# OPENMV4_BASE.net
KiCad netlist of a schematic drawn in Altium Designer
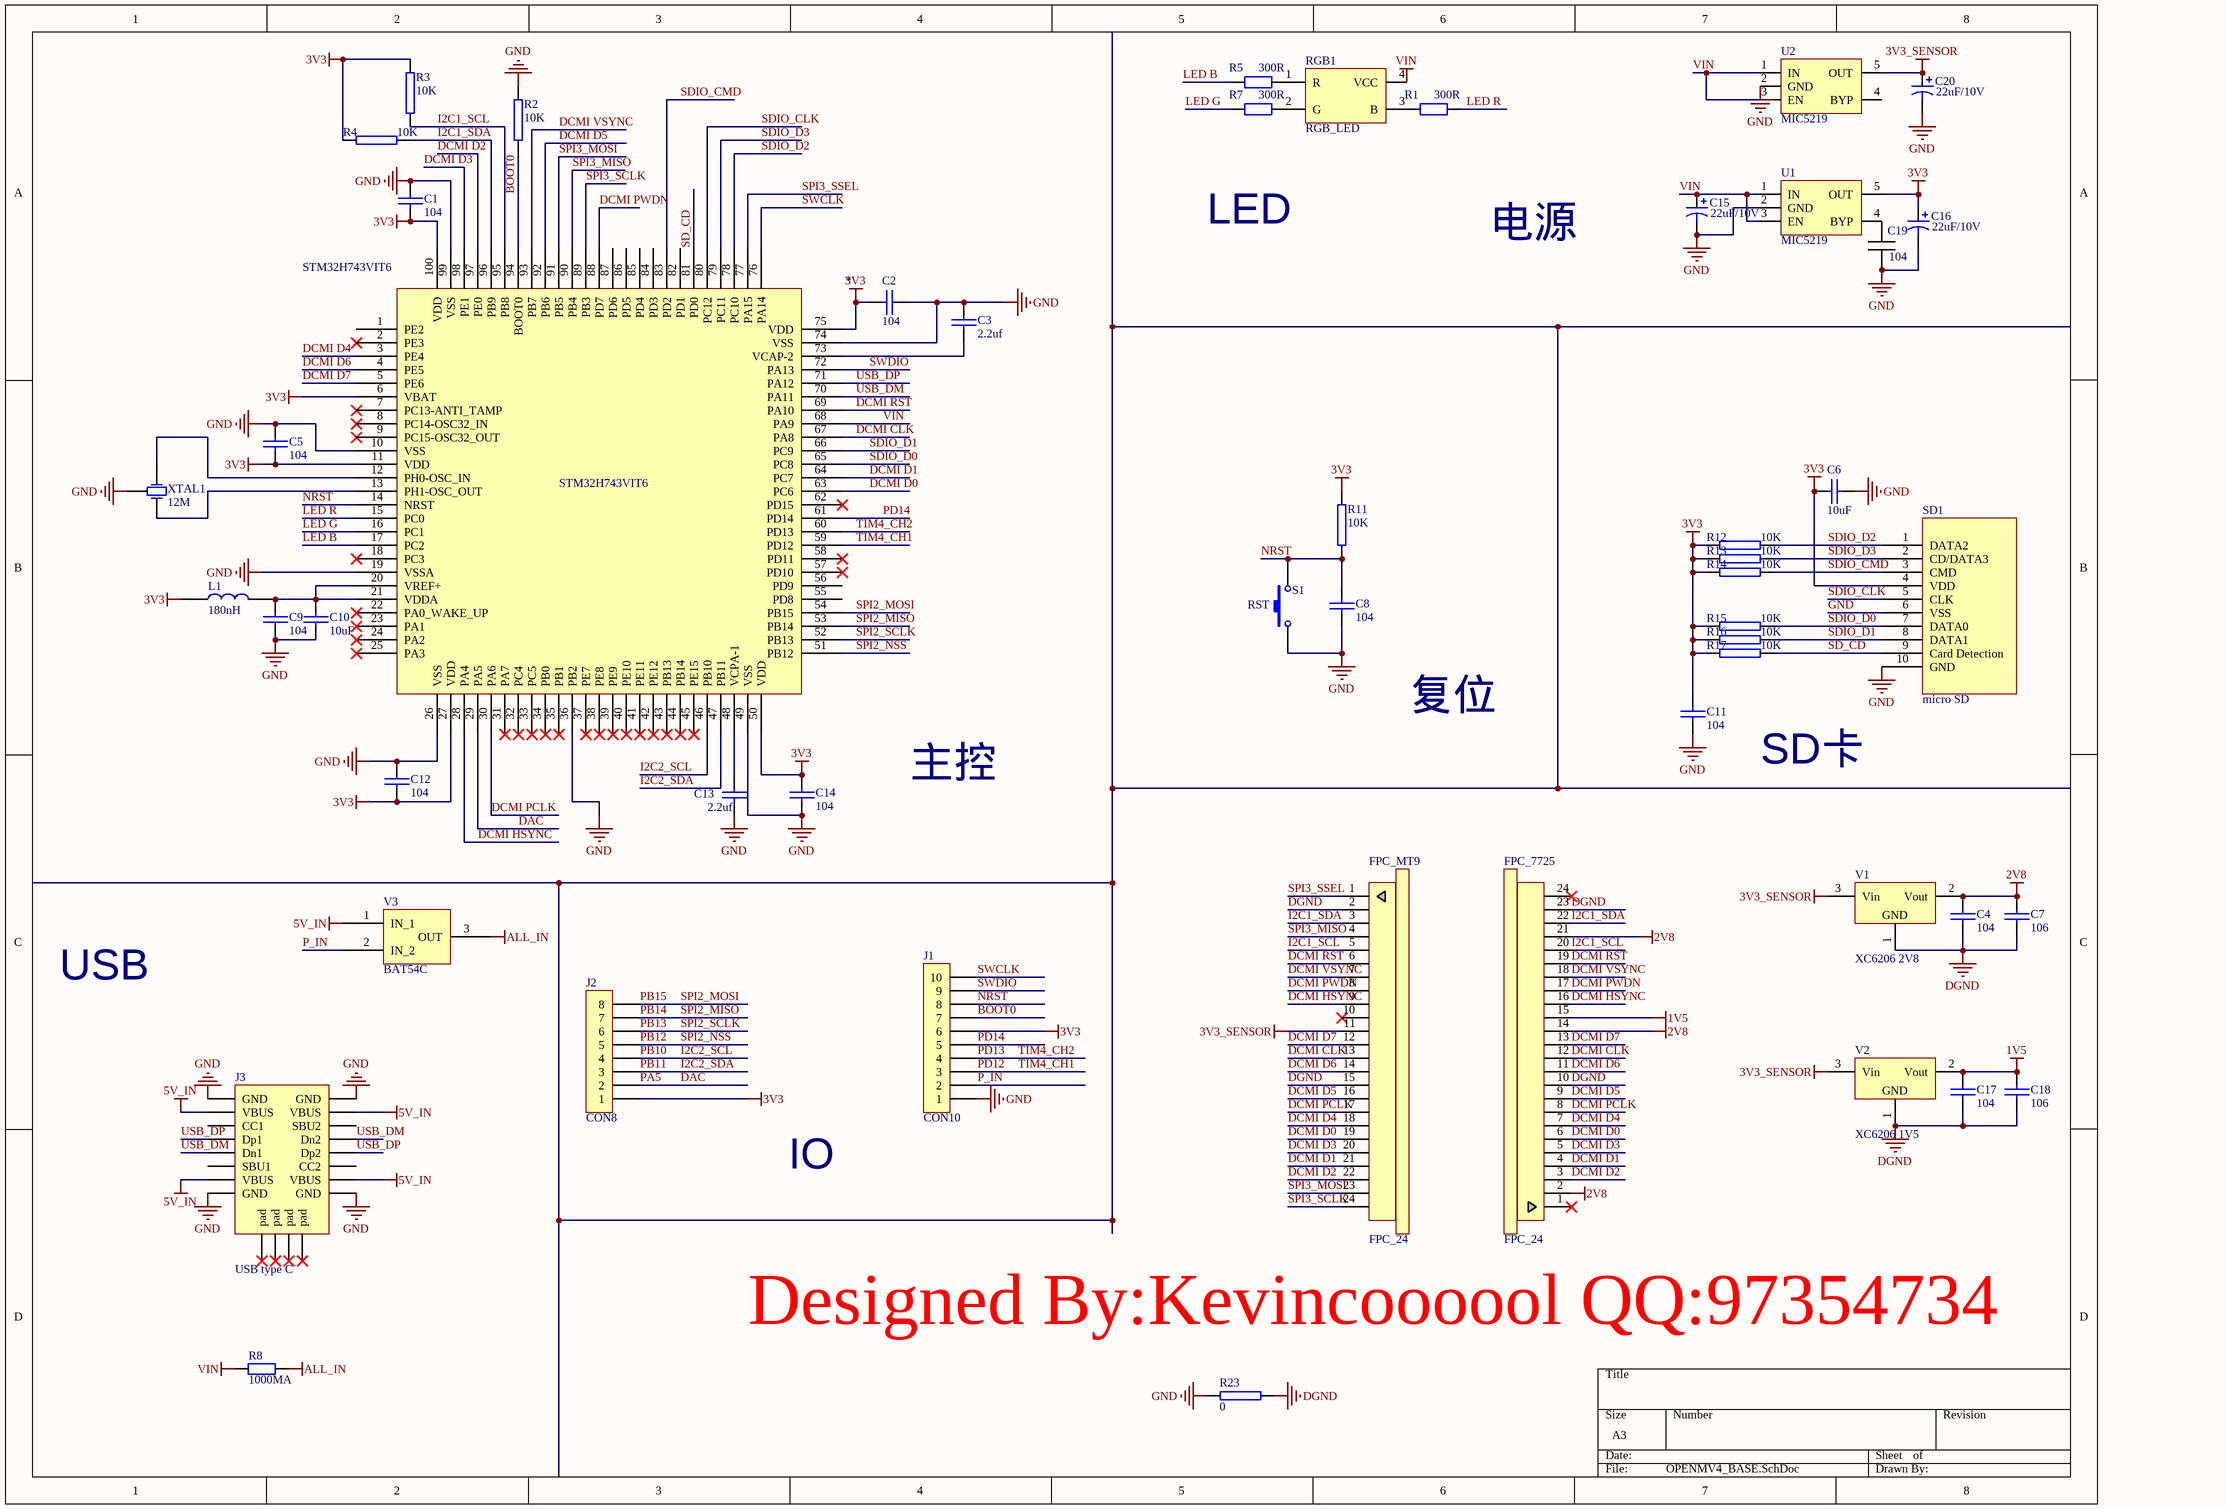
[diagram p0: OPENMV4_BASE.SchDoc]

(export (version "E")
  (design (tool "Eeschema 10.0.6"))
  (components
    (comp (ref "*")
      (value "STM32H743VIT6")
      (footprint "LQFP100 14x14_N")
      (libsource (lib "XKZ") (part "STM32H743VIT6"))
    )
    (comp (ref "C1") (value "104") (footprint "LC-0603_C") (libsource (lib "自创 (1)") (part "CAP")))
    (comp (ref "C2") (value "104") (footprint "LC-0603_C") (libsource (lib "自创 (1)") (part "CAP")))
    (comp (ref "C3") (value "2.2uf") (footprint "LC-0603_C") (libsource (lib "自创 (1)") (part "CAP")))
    (comp (ref "C4") (value "104") (footprint "0603_C") (libsource (lib "XKZ") (part "CAP")))
    (comp (ref "C5") (value "104") (footprint "LC-0603_C") (libsource (lib "自创 (1)") (part "CAP")))
    (comp (ref "C6") (value "10uF") (footprint "LC-0805_C") (libsource (lib "自创 (1)") (part "CAP")))
    (comp (ref "C7") (value "106") (footprint "0603_C") (libsource (lib "XKZ") (part "CAP")))
    (comp (ref "C8") (value "104") (footprint "LC-0603_C") (libsource (lib "自创 (1)") (part "CAP")))
    (comp (ref "C9") (value "104") (footprint "LC-0603_C") (libsource (lib "自创 (1)") (part "CAP")))
    (comp (ref "C10") (value "10uF") (footprint "LC-0603_C") (libsource (lib "自创 (1)") (part "CAP")))
    (comp (ref "C11") (value "104") (footprint "LC-0603_C") (libsource (lib "自创 (1)") (part "CAP")))
    (comp (ref "C12") (value "104") (footprint "LC-0603_C") (libsource (lib "自创 (1)") (part "CAP")))
    (comp (ref "C13") (value "2.2uf") (footprint "LC-0603_C") (libsource (lib "自创 (1)") (part "CAP")))
    (comp (ref "C14") (value "104") (footprint "LC-0603_C") (libsource (lib "自创 (1)") (part "CAP")))
    (comp (ref "C15")
      (value "22uF/10V")
      (footprint "LC-1206_C")
      (description "Polarized Capacitor (Radial)")
      (fields (field (name "Comment") "47uF") (field (name "PUBLISHER") "Altium Limited"))
      (libsource (lib "Miscellaneous Devices") (part "Cap Pol1"))
    )
    (comp (ref "C16")
      (value "22uF/10V")
      (footprint "LC-1206_C")
      (description "Polarized Capacitor (Radial)")
      (fields (field (name "Comment") "47uF") (field (name "PUBLISHER") "Altium Limited"))
      (libsource (lib "Miscellaneous Devices") (part "Cap Pol1"))
    )
    (comp (ref "C17") (value "104") (footprint "0603_C") (libsource (lib "XKZ") (part "CAP")))
    (comp (ref "C18") (value "106") (footprint "0603_C") (libsource (lib "XKZ") (part "CAP")))
    (comp (ref "C19") (value "104") (footprint "LC-0603_C") (libsource (lib "NT-SchLibrary") (part "CAP104")))
    (comp (ref "C20")
      (value "22uF/10V")
      (footprint "LC-1206_C")
      (description "Polarized Capacitor (Radial)")
      (fields (field (name "Comment") "47uF") (field (name "PUBLISHER") "Altium Limited"))
      (libsource (lib "Miscellaneous Devices") (part "Cap Pol1"))
    )
    (comp (ref "FPC_7725") (value "FPC_24") (footprint "FPC_24") (libsource (lib "") (part "FPC_24_1")))
    (comp (ref "FPC_MT9") (value "FPC_24") (footprint "FPC_24") (libsource (lib "XKZ") (part "FPC_24")))
    (comp (ref "J1") (value "CON10") (footprint "HDR1X10") (libsource (lib "自创") (part "CON10")))
    (comp (ref "J2") (value "CON8") (footprint "HDR1X8") (libsource (lib "自创") (part "CON8")))
    (comp (ref "J3")
      (value "USB type C")
      (footprint "USB Type-C-16Pin_A")
      (libsource (lib "XKZ") (part "USB_C"))
    )
    (comp (ref "L1") (value "180nH") (footprint "LC-0603_L") (libsource (lib "自创 (1)") (part "Inductor")))
    (comp (ref "R1")
      (value "300R")
      (footprint "0603_R")
      (description "Resistor")
      (fields (field (name "Comment") "1K") (field (name "PUBLISHER") "Altium Limited"))
      (libsource (lib "Miscellaneous Devices") (part "Res2"))
    )
    (comp (ref "R2") (value "10K") (footprint "LC-0603_R") (libsource (lib "自创 (1)") (part "RES")))
    (comp (ref "R3") (value "10K") (footprint "LC-0603_R") (libsource (lib "自创 (1)") (part "RES")))
    (comp (ref "R4") (value "10K") (footprint "LC-0603_R") (libsource (lib "自创 (1)") (part "RES")))
    (comp (ref "R5")
      (value "300R")
      (footprint "0603_R")
      (description "Resistor")
      (fields (field (name "Comment") "1K") (field (name "PUBLISHER") "Altium Limited"))
      (libsource (lib "Miscellaneous Devices") (part "Res2"))
    )
    (comp (ref "R7")
      (value "300R")
      (footprint "0603_R")
      (description "Resistor")
      (fields (field (name "Comment") "1K") (field (name "PUBLISHER") "Altium Limited"))
      (libsource (lib "Miscellaneous Devices") (part "Res2"))
    )
    (comp (ref "R8")
      (value "1000MA")
      (footprint "LC-0805_L")
      (description "Resistor")
      (fields (field (name "Comment") "1A保险丝") (field (name "PUBLISHER") "Altium Limited"))
      (libsource (lib "XKZ") (part "Res2"))
    )
    (comp (ref "R11") (value "10K") (footprint "LC-0603_R") (libsource (lib "自创 (1)") (part "RES")))
    (comp (ref "R12") (value "10K") (footprint "LC-0603_R") (libsource (lib "自创 (1)") (part "RES")))
    (comp (ref "R13") (value "10K") (footprint "LC-0603_R") (libsource (lib "自创 (1)") (part "RES")))
    (comp (ref "R14") (value "10K") (footprint "LC-0603_R") (libsource (lib "自创 (1)") (part "RES")))
    (comp (ref "R15") (value "10K") (footprint "LC-0603_R") (libsource (lib "自创 (1)") (part "RES")))
    (comp (ref "R16") (value "10K") (footprint "LC-0603_R") (libsource (lib "自创 (1)") (part "RES")))
    (comp (ref "R17") (value "10K") (footprint "LC-0603_R") (libsource (lib "自创 (1)") (part "RES")))
    (comp (ref "R23") (value "0") (footprint "LC-0603_R") (libsource (lib "自创 (1)") (part "RES")))
    (comp (ref "RGB1")
      (value "RGB_LED")
      (footprint "LED_3528_RGB")
      (description "三色高亮LED")
      (libsource (lib "NT-SchLibrary") (part "RGB_LED"))
    )
    (comp (ref "S1")
      (value "RST")
      (footprint "KEY_1")
      (description "Switch")
      (fields (field (name "PUBLISHER") "Altium Limited"))
      (libsource (lib "自创 (1)") (part "SW-PB"))
    )
    (comp (ref "SD1") (value "micro SD") (footprint "TF卡座") (libsource (lib "XKZ") (part "micro SD")))
    (comp (ref "U1")
      (value "MIC5219")
      (footprint "SOT23-5N")
      (description "3.3V 降压芯片")
      (libsource (lib "NT-SchLibrary") (part "MIC5219"))
    )
    (comp (ref "U2")
      (value "MIC5219")
      (footprint "SOT23-5N")
      (description "3.3V 降压芯片")
      (libsource (lib "NT-SchLibrary") (part "MIC5219"))
    )
    (comp (ref "V1")
      (value "XC6206 2V8")
      (footprint "SOT23-3N")
      (description "低压差线性稳压芯片")
      (fields (field (name "版权归属") "源创客"))
      (libsource (lib "XKZ") (part "XC6206P332MR"))
    )
    (comp (ref "V2")
      (value "XC6206 1V5")
      (footprint "SOT23-3N")
      (description "低压差线性稳压芯片")
      (fields (field (name "版权归属") "源创客"))
      (libsource (lib "XKZ") (part "XC6206P332MR"))
    )
    (comp (ref "V3") (value "BAT54C") (footprint "SOT23-3N") (libsource (lib "XKZ") (part "BAT54C")))
    (comp (ref "XTAL1") (value "12M") (footprint "XTAL-3215-3P") (libsource (lib "XKZ") (part "XTAL_3P")))
  )
  (nets
    (net (code "1") (name "/BOOT0") (class "Default")
      (node (ref "*") (pin "94") (pinfunction "BOOT0_94") (pintype "passive"))
      (node (ref "J1") (pin "7") (pinfunction "7_7") (pintype "passive"))
      (node (ref "R2") (pin "1") (pinfunction "1_1") (pintype "passive"))
    )
    (net (code "2") (name "/DAC") (class "Default")
      (node (ref "*") (pin "29") (pinfunction "PA5_29") (pintype "passive"))
      (node (ref "J2") (pin "2") (pinfunction "2_2") (pintype "passive"))
    )
    (net (code "3") (name "/DCMI CLK") (class "Default")
      (node (ref "*") (pin "67") (pinfunction "PA8_67") (pintype "passive"))
      (node (ref "FPC_7725") (pin "12") (pinfunction "12_12") (pintype "passive"))
      (node (ref "FPC_MT9") (pin "13") (pinfunction "13_13") (pintype "passive"))
    )
    (net (code "4") (name "/DCMI D0") (class "Default")
      (node (ref "*") (pin "63") (pinfunction "PC6_63") (pintype "passive"))
      (node (ref "FPC_7725") (pin "6") (pinfunction "6_6") (pintype "passive"))
      (node (ref "FPC_MT9") (pin "19") (pinfunction "19_19") (pintype "passive"))
    )
    (net (code "5") (name "/DCMI D1") (class "Default")
      (node (ref "*") (pin "64") (pinfunction "PC7_64") (pintype "passive"))
      (node (ref "FPC_7725") (pin "4") (pinfunction "4_4") (pintype "passive"))
      (node (ref "FPC_MT9") (pin "21") (pinfunction "21_21") (pintype "passive"))
    )
    (net (code "6") (name "/DCMI D2") (class "Default")
      (node (ref "*") (pin "97") (pinfunction "PE0_97") (pintype "passive"))
      (node (ref "FPC_7725") (pin "3") (pinfunction "3_3") (pintype "passive"))
      (node (ref "FPC_MT9") (pin "22") (pinfunction "22_22") (pintype "passive"))
    )
    (net (code "7") (name "/DCMI D3") (class "Default")
      (node (ref "*") (pin "98") (pinfunction "PE1_98") (pintype "passive"))
      (node (ref "FPC_7725") (pin "5") (pinfunction "5_5") (pintype "passive"))
      (node (ref "FPC_MT9") (pin "20") (pinfunction "20_20") (pintype "passive"))
    )
    (net (code "8") (name "/DCMI D4") (class "Default")
      (node (ref "*") (pin "3") (pinfunction "PE4_3") (pintype "passive"))
      (node (ref "FPC_7725") (pin "7") (pinfunction "7_7") (pintype "passive"))
      (node (ref "FPC_MT9") (pin "18") (pinfunction "18_18") (pintype "passive"))
    )
    (net (code "9") (name "/DCMI D5") (class "Default")
      (node (ref "*") (pin "92") (pinfunction "PB6_92") (pintype "passive"))
      (node (ref "FPC_7725") (pin "9") (pinfunction "9_9") (pintype "passive"))
      (node (ref "FPC_MT9") (pin "16") (pinfunction "16_16") (pintype "passive"))
    )
    (net (code "10") (name "/DCMI D6") (class "Default")
      (node (ref "*") (pin "4") (pinfunction "PE5_4") (pintype "passive"))
      (node (ref "FPC_7725") (pin "11") (pinfunction "11_11") (pintype "passive"))
      (node (ref "FPC_MT9") (pin "14") (pinfunction "14_14") (pintype "passive"))
    )
    (net (code "11") (name "/DCMI D7") (class "Default")
      (node (ref "*") (pin "5") (pinfunction "PE6_5") (pintype "passive"))
      (node (ref "FPC_7725") (pin "13") (pinfunction "13_13") (pintype "passive"))
      (node (ref "FPC_MT9") (pin "12") (pinfunction "12_12") (pintype "passive"))
    )
    (net (code "12") (name "/DCMI HSYNC") (class "Default")
      (node (ref "*") (pin "28") (pinfunction "PA4_28") (pintype "passive"))
      (node (ref "FPC_7725") (pin "16") (pinfunction "16_16") (pintype "passive"))
      (node (ref "FPC_MT9") (pin "9") (pinfunction "9_9") (pintype "passive"))
    )
    (net (code "13") (name "/DCMI PCLK") (class "Default")
      (node (ref "*") (pin "30") (pinfunction "PA6_30") (pintype "passive"))
      (node (ref "FPC_7725") (pin "8") (pinfunction "8_8") (pintype "passive"))
      (node (ref "FPC_MT9") (pin "17") (pinfunction "17_17") (pintype "passive"))
    )
    (net (code "14") (name "/DCMI PWDN") (class "Default")
      (node (ref "*") (pin "88") (pinfunction "PD7_88") (pintype "passive"))
      (node (ref "FPC_7725") (pin "17") (pinfunction "17_17") (pintype "passive"))
      (node (ref "FPC_MT9") (pin "8") (pinfunction "8_8") (pintype "passive"))
    )
    (net (code "15") (name "/DCMI RST") (class "Default")
      (node (ref "*") (pin "69") (pinfunction "PA10_69") (pintype "passive"))
      (node (ref "FPC_7725") (pin "19") (pinfunction "19_19") (pintype "passive"))
      (node (ref "FPC_MT9") (pin "6") (pinfunction "6_6") (pintype "passive"))
    )
    (net (code "16") (name "/DCMI VSYNC") (class "Default")
      (node (ref "*") (pin "93") (pinfunction "PB7_93") (pintype "passive"))
      (node (ref "FPC_7725") (pin "18") (pinfunction "18_18") (pintype "passive"))
      (node (ref "FPC_MT9") (pin "7") (pinfunction "7_7") (pintype "passive"))
    )
    (net (code "17") (name "/I2C1_SCL") (class "Default")
      (node (ref "*") (pin "95") (pinfunction "PB8_95") (pintype "passive"))
      (node (ref "FPC_7725") (pin "20") (pinfunction "20_20") (pintype "passive"))
      (node (ref "FPC_MT9") (pin "5") (pinfunction "5_5") (pintype "passive"))
      (node (ref "R3") (pin "1") (pinfunction "1_1") (pintype "passive"))
    )
    (net (code "18") (name "/I2C1_SDA") (class "Default")
      (node (ref "*") (pin "96") (pinfunction "PB9_96") (pintype "passive"))
      (node (ref "FPC_7725") (pin "22") (pinfunction "22_22") (pintype "passive"))
      (node (ref "FPC_MT9") (pin "3") (pinfunction "3_3") (pintype "passive"))
      (node (ref "R4") (pin "2") (pinfunction "2_2") (pintype "passive"))
    )
    (net (code "19") (name "/I2C2_SCL") (class "Default")
      (node (ref "*") (pin "46") (pinfunction "PB10_46") (pintype "passive"))
      (node (ref "J2") (pin "4") (pinfunction "4_4") (pintype "passive"))
    )
    (net (code "20") (name "/I2C2_SDA") (class "Default")
      (node (ref "*") (pin "47") (pinfunction "PB11_47") (pintype "passive"))
      (node (ref "J2") (pin "3") (pinfunction "3_3") (pintype "passive"))
    )
    (net (code "21") (name "/LED B") (class "Default")
      (node (ref "*") (pin "17") (pinfunction "PC2_17") (pintype "passive"))
      (node (ref "R5") (pin "1") (pinfunction "1_1") (pintype "passive"))
    )
    (net (code "22") (name "/LED G") (class "Default")
      (node (ref "*") (pin "16") (pinfunction "PC1_16") (pintype "passive"))
      (node (ref "R7") (pin "1") (pinfunction "1_1") (pintype "passive"))
    )
    (net (code "23") (name "/LED R") (class "Default")
      (node (ref "*") (pin "15") (pinfunction "PC0_15") (pintype "passive"))
      (node (ref "R1") (pin "2") (pinfunction "2_2") (pintype "passive"))
    )
    (net (code "24") (name "/NRST") (class "Default")
      (node (ref "*") (pin "14") (pinfunction "NRST_14") (pintype "passive"))
      (node (ref "C8") (pin "2") (pinfunction "2_2") (pintype "passive"))
      (node (ref "J1") (pin "8") (pinfunction "8_8") (pintype "passive"))
      (node (ref "R11") (pin "2") (pinfunction "2_2") (pintype "passive"))
      (node (ref "S1") (pin "2") (pinfunction "2_2") (pintype "passive"))
    )
    (net (code "25") (name "/PB12") (class "Default")
      (node (ref "*") (pin "51") (pinfunction "PB12_51") (pintype "passive"))
      (node (ref "J2") (pin "5") (pinfunction "5_5") (pintype "passive"))
    )
    (net (code "26") (name "/PB13") (class "Default")
      (node (ref "*") (pin "52") (pinfunction "PB13_52") (pintype "passive"))
      (node (ref "J2") (pin "6") (pinfunction "6_6") (pintype "passive"))
    )
    (net (code "27") (name "/PB14") (class "Default")
      (node (ref "*") (pin "53") (pinfunction "PB14_53") (pintype "passive"))
      (node (ref "J2") (pin "7") (pinfunction "7_7") (pintype "passive"))
    )
    (net (code "28") (name "/PB15") (class "Default")
      (node (ref "*") (pin "54") (pinfunction "PB15_54") (pintype "passive"))
      (node (ref "J2") (pin "8") (pinfunction "8_8") (pintype "passive"))
    )
    (net (code "29") (name "/PD12") (class "Default")
      (node (ref "*") (pin "59") (pinfunction "PD12_59") (pintype "passive"))
      (node (ref "J1") (pin "3") (pinfunction "3_3") (pintype "passive"))
    )
    (net (code "30") (name "/PD13") (class "Default")
      (node (ref "*") (pin "60") (pinfunction "PD13_60") (pintype "passive"))
      (node (ref "J1") (pin "4") (pinfunction "4_4") (pintype "passive"))
    )
    (net (code "31") (name "/PD14") (class "Default")
      (node (ref "*") (pin "61") (pinfunction "PD14_61") (pintype "passive"))
      (node (ref "J1") (pin "5") (pinfunction "5_5") (pintype "passive"))
    )
    (net (code "32") (name "/P_IN") (class "Default")
      (node (ref "J1") (pin "2") (pinfunction "2_2") (pintype "passive"))
      (node (ref "V3") (pin "2") (pinfunction "IN_2_2") (pintype "passive"))
    )
    (net (code "33") (name "/SDIO_CLK") (class "Default")
      (node (ref "*") (pin "80") (pinfunction "PC12_80") (pintype "passive"))
      (node (ref "SD1") (pin "5") (pinfunction "CLK_5") (pintype "passive"))
    )
    (net (code "34") (name "/SDIO_CMD") (class "Default")
      (node (ref "*") (pin "83") (pinfunction "PD2_83") (pintype "passive"))
      (node (ref "R14") (pin "2") (pinfunction "2_2") (pintype "passive"))
      (node (ref "SD1") (pin "3") (pinfunction "CMD_3") (pintype "passive"))
    )
    (net (code "35") (name "/SDIO_D0") (class "Default")
      (node (ref "*") (pin "65") (pinfunction "PC8_65") (pintype "passive"))
      (node (ref "R15") (pin "2") (pinfunction "2_2") (pintype "passive"))
      (node (ref "SD1") (pin "7") (pinfunction "DATA0_7") (pintype "passive"))
    )
    (net (code "36") (name "/SDIO_D1") (class "Default")
      (node (ref "*") (pin "66") (pinfunction "PC9_66") (pintype "passive"))
      (node (ref "R16") (pin "2") (pinfunction "2_2") (pintype "passive"))
      (node (ref "SD1") (pin "8") (pinfunction "DATA1_8") (pintype "passive"))
    )
    (net (code "37") (name "/SDIO_D2") (class "Default")
      (node (ref "*") (pin "78") (pinfunction "PC10_78") (pintype "passive"))
      (node (ref "R12") (pin "2") (pinfunction "2_2") (pintype "passive"))
      (node (ref "SD1") (pin "1") (pinfunction "DATA2_1") (pintype "passive"))
    )
    (net (code "38") (name "/SDIO_D3") (class "Default")
      (node (ref "*") (pin "79") (pinfunction "PC11_79") (pintype "passive"))
      (node (ref "R13") (pin "2") (pinfunction "2_2") (pintype "passive"))
      (node (ref "SD1") (pin "2") (pinfunction "CD/DATA3_2") (pintype "passive"))
    )
    (net (code "39") (name "/SD_CD") (class "Default")
      (node (ref "*") (pin "81") (pinfunction "PD0_81") (pintype "passive"))
      (node (ref "R17") (pin "2") (pinfunction "2_2") (pintype "passive"))
      (node (ref "SD1") (pin "9") (pinfunction "Card_Detection_9") (pintype "passive"))
    )
    (net (code "40") (name "/SPI3_MISO") (class "Default")
      (node (ref "*") (pin "90") (pinfunction "PB4_90") (pintype "passive"))
      (node (ref "FPC_MT9") (pin "4") (pinfunction "4_4") (pintype "passive"))
    )
    (net (code "41") (name "/SPI3_MOSI") (class "Default")
      (node (ref "*") (pin "91") (pinfunction "PB5_91") (pintype "passive"))
      (node (ref "FPC_MT9") (pin "23") (pinfunction "23_23") (pintype "passive"))
    )
    (net (code "42") (name "/SPI3_SCLK") (class "Default")
      (node (ref "*") (pin "89") (pinfunction "PB3_89") (pintype "passive"))
      (node (ref "FPC_MT9") (pin "24") (pinfunction "24_24") (pintype "passive"))
    )
    (net (code "43") (name "/SPI3_SSEL") (class "Default")
      (node (ref "*") (pin "77") (pinfunction "PA15_77") (pintype "passive"))
      (node (ref "FPC_MT9") (pin "1") (pinfunction "1_1") (pintype "passive"))
    )
    (net (code "44") (name "/SWCLK") (class "Default")
      (node (ref "*") (pin "76") (pinfunction "PA14_76") (pintype "passive"))
      (node (ref "J1") (pin "10") (pinfunction "10_10") (pintype "passive"))
    )
    (net (code "45") (name "/SWDIO") (class "Default")
      (node (ref "*") (pin "72") (pinfunction "PA13_72") (pintype "passive"))
      (node (ref "J1") (pin "9") (pinfunction "9_9") (pintype "passive"))
    )
    (net (code "46") (name "/USB_DM") (class "Default")
      (node (ref "*") (pin "70") (pinfunction "PA11_70") (pintype "passive"))
      (node (ref "J3") (pin "A7") (pinfunction "Dn1_A7") (pintype "passive"))
      (node (ref "J3") (pin "B7") (pinfunction "Dn2_B7") (pintype "passive"))
    )
    (net (code "47") (name "/USB_DP") (class "Default")
      (node (ref "*") (pin "71") (pinfunction "PA12_71") (pintype "passive"))
      (node (ref "J3") (pin "A6") (pinfunction "Dp1_A6") (pintype "passive"))
      (node (ref "J3") (pin "B6") (pinfunction "Dp2_B6") (pintype "passive"))
    )
    (net (code "48") (name "1V5") (class "Default")
      (node (ref "C17") (pin "1") (pinfunction "1_1") (pintype "passive"))
      (node (ref "C18") (pin "1") (pinfunction "1_1") (pintype "passive"))
      (node (ref "FPC_7725") (pin "15") (pinfunction "15_15") (pintype "passive"))
      (node (ref "V2") (pin "2") (pinfunction "Vout_2") (pintype "passive"))
    )
    (net (code "49") (name "2V8") (class "Default")
      (node (ref "C4") (pin "1") (pinfunction "1_1") (pintype "passive"))
      (node (ref "C7") (pin "1") (pinfunction "1_1") (pintype "passive"))
      (node (ref "FPC_7725") (pin "14") (pinfunction "14_14") (pintype "passive"))
      (node (ref "FPC_7725") (pin "2") (pinfunction "2_2") (pintype "passive"))
      (node (ref "FPC_7725") (pin "21") (pinfunction "21_21") (pintype "passive"))
      (node (ref "V1") (pin "2") (pinfunction "Vout_2") (pintype "passive"))
    )
    (net (code "50") (name "3V3") (class "Default")
      (node (ref "*") (pin "100") (pinfunction "VDD_100") (pintype "passive"))
      (node (ref "*") (pin "11") (pinfunction "VDD_11") (pintype "passive"))
      (node (ref "*") (pin "27") (pinfunction "VDD_27") (pintype "passive"))
      (node (ref "*") (pin "50") (pinfunction "VDD_50") (pintype "passive"))
      (node (ref "*") (pin "6") (pinfunction "VBAT_6") (pintype "passive"))
      (node (ref "*") (pin "75") (pinfunction "VDD_75") (pintype "passive"))
      (node (ref "C1") (pin "2") (pinfunction "2_2") (pintype "passive"))
      (node (ref "C11") (pin "2") (pinfunction "2_2") (pintype "passive"))
      (node (ref "C12") (pin "2") (pinfunction "2_2") (pintype "passive"))
      (node (ref "C14") (pin "2") (pinfunction "2_2") (pintype "passive"))
      (node (ref "C16") (pin "1") (pinfunction "1_1") (pintype "passive"))
      (node (ref "C2") (pin "2") (pinfunction "2_2") (pintype "passive"))
      (node (ref "C5") (pin "2") (pinfunction "2_2") (pintype "passive"))
      (node (ref "C6") (pin "2") (pinfunction "2_2") (pintype "passive"))
      (node (ref "J1") (pin "6") (pinfunction "6_6") (pintype "passive"))
      (node (ref "J2") (pin "1") (pinfunction "1_1") (pintype "passive"))
      (node (ref "L1") (pin "1") (pinfunction "1_1") (pintype "passive"))
      (node (ref "R11") (pin "1") (pinfunction "1_1") (pintype "passive"))
      (node (ref "R12") (pin "1") (pinfunction "1_1") (pintype "passive"))
      (node (ref "R13") (pin "1") (pinfunction "1_1") (pintype "passive"))
      (node (ref "R14") (pin "1") (pinfunction "1_1") (pintype "passive"))
      (node (ref "R15") (pin "1") (pinfunction "1_1") (pintype "passive"))
      (node (ref "R16") (pin "1") (pinfunction "1_1") (pintype "passive"))
      (node (ref "R17") (pin "1") (pinfunction "1_1") (pintype "passive"))
      (node (ref "R3") (pin "2") (pinfunction "2_2") (pintype "passive"))
      (node (ref "R4") (pin "1") (pinfunction "1_1") (pintype "passive"))
      (node (ref "SD1") (pin "4") (pinfunction "VDD_4") (pintype "passive"))
      (node (ref "U1") (pin "5") (pinfunction "OUT_5") (pintype "passive"))
    )
    (net (code "51") (name "3V3_SENSOR") (class "Default")
      (node (ref "C20") (pin "1") (pinfunction "1_1") (pintype "passive"))
      (node (ref "FPC_MT9") (pin "11") (pinfunction "11_11") (pintype "passive"))
      (node (ref "U2") (pin "5") (pinfunction "OUT_5") (pintype "passive"))
      (node (ref "V1") (pin "3") (pinfunction "Vin_3") (pintype "passive"))
      (node (ref "V2") (pin "3") (pinfunction "Vin_3") (pintype "passive"))
    )
    (net (code "52") (name "5V_IN") (class "Default")
      (node (ref "J3") (pin "A4") (pinfunction "VBUS_A4") (pintype "passive"))
      (node (ref "J3") (pin "A9") (pinfunction "VBUS_A9") (pintype "passive"))
      (node (ref "J3") (pin "B4") (pinfunction "VBUS_B4") (pintype "passive"))
      (node (ref "J3") (pin "B9") (pinfunction "VBUS_B9") (pintype "passive"))
      (node (ref "V3") (pin "1") (pinfunction "IN_1_1") (pintype "passive"))
    )
    (net (code "53") (name "ALL_IN") (class "Default")
      (node (ref "R8") (pin "2") (pinfunction "2_2") (pintype "passive"))
      (node (ref "V3") (pin "3") (pinfunction "OUT_3") (pintype "passive"))
    )
    (net (code "54") (name "DGND") (class "Default")
      (node (ref "C17") (pin "2") (pinfunction "2_2") (pintype "passive"))
      (node (ref "C18") (pin "2") (pinfunction "2_2") (pintype "passive"))
      (node (ref "C4") (pin "2") (pinfunction "2_2") (pintype "passive"))
      (node (ref "C7") (pin "2") (pinfunction "2_2") (pintype "passive"))
      (node (ref "FPC_7725") (pin "10") (pinfunction "10_10") (pintype "passive"))
      (node (ref "FPC_7725") (pin "23") (pinfunction "23_23") (pintype "passive"))
      (node (ref "FPC_MT9") (pin "15") (pinfunction "15_15") (pintype "passive"))
      (node (ref "FPC_MT9") (pin "2") (pinfunction "2_2") (pintype "passive"))
      (node (ref "R23") (pin "2") (pinfunction "2_2") (pintype "passive"))
      (node (ref "V1") (pin "1") (pinfunction "GND_1") (pintype "passive"))
      (node (ref "V2") (pin "1") (pinfunction "GND_1") (pintype "passive"))
    )
    (net (code "55") (name "GND") (class "Default")
      (node (ref "*") (pin "10") (pinfunction "VSS_10") (pintype "passive"))
      (node (ref "*") (pin "19") (pinfunction "VSSA_19") (pintype "passive"))
      (node (ref "*") (pin "26") (pinfunction "VSS_26") (pintype "passive"))
      (node (ref "*") (pin "36") (pinfunction "PB2_36") (pintype "passive"))
      (node (ref "*") (pin "49") (pinfunction "VSS_49") (pintype "passive"))
      (node (ref "*") (pin "74") (pinfunction "VSS_74") (pintype "passive"))
      (node (ref "*") (pin "99") (pinfunction "VSS_99") (pintype "passive"))
      (node (ref "C1") (pin "1") (pinfunction "1_1") (pintype "passive"))
      (node (ref "C10") (pin "2") (pinfunction "2_2") (pintype "passive"))
      (node (ref "C11") (pin "1") (pinfunction "1_1") (pintype "passive"))
      (node (ref "C12") (pin "1") (pinfunction "1_1") (pintype "passive"))
      (node (ref "C13") (pin "2") (pinfunction "2_2") (pintype "passive"))
      (node (ref "C14") (pin "1") (pinfunction "1_1") (pintype "passive"))
      (node (ref "C15") (pin "2") (pinfunction "2_2") (pintype "passive"))
      (node (ref "C16") (pin "2") (pinfunction "2_2") (pintype "passive"))
      (node (ref "C19") (pin "1") (pinfunction "1_1") (pintype "passive"))
      (node (ref "C2") (pin "1") (pinfunction "1_1") (pintype "passive"))
      (node (ref "C20") (pin "2") (pinfunction "2_2") (pintype "passive"))
      (node (ref "C3") (pin "2") (pinfunction "2_2") (pintype "passive"))
      (node (ref "C5") (pin "1") (pinfunction "1_1") (pintype "passive"))
      (node (ref "C6") (pin "1") (pinfunction "1_1") (pintype "passive"))
      (node (ref "C8") (pin "1") (pinfunction "1_1") (pintype "passive"))
      (node (ref "C9") (pin "2") (pinfunction "2_2") (pintype "passive"))
      (node (ref "J1") (pin "1") (pinfunction "1_1") (pintype "passive"))
      (node (ref "J3") (pin "A1") (pinfunction "GND_A1") (pintype "passive"))
      (node (ref "J3") (pin "A12") (pinfunction "GND_A12") (pintype "passive"))
      (node (ref "J3") (pin "B1") (pinfunction "GND_B1") (pintype "passive"))
      (node (ref "J3") (pin "B12") (pinfunction "GND_B12") (pintype "passive"))
      (node (ref "R2") (pin "2") (pinfunction "2_2") (pintype "passive"))
      (node (ref "R23") (pin "1") (pinfunction "1_1") (pintype "passive"))
      (node (ref "S1") (pin "1") (pinfunction "1_1") (pintype "passive"))
      (node (ref "SD1") (pin "10") (pinfunction "GND_10") (pintype "passive"))
      (node (ref "SD1") (pin "6") (pinfunction "VSS_6") (pintype "passive"))
      (node (ref "U1") (pin "2") (pinfunction "GND_2") (pintype "passive"))
      (node (ref "U2") (pin "2") (pinfunction "GND_2") (pintype "passive"))
      (node (ref "XTAL1") (pin "2") (pinfunction "2_2") (pintype "passive"))
    )
    (net (code "56") (name "Net-(*-PH0-OSC_IN)") (class "Default")
      (node (ref "*") (pin "12") (pinfunction "PH0-OSC_IN_12") (pintype "passive"))
      (node (ref "XTAL1") (pin "1") (pinfunction "1_1") (pintype "passive"))
    )
    (net (code "57") (name "Net-(*-PH1-OSC_OUT)") (class "Default")
      (node (ref "*") (pin "13") (pinfunction "PH1-OSC_OUT_13") (pintype "passive"))
      (node (ref "XTAL1") (pin "3") (pinfunction "3_3") (pintype "passive"))
    )
    (net (code "58") (name "Net-(*-VCAP-2)") (class "Default")
      (node (ref "*") (pin "73") (pinfunction "VCAP-2_73") (pintype "passive"))
      (node (ref "C3") (pin "1") (pinfunction "1_1") (pintype "passive"))
    )
    (net (code "59") (name "Net-(*-VCPA-1)") (class "Default")
      (node (ref "*") (pin "48") (pinfunction "VCPA-1_48") (pintype "passive"))
      (node (ref "C13") (pin "1") (pinfunction "1_1") (pintype "passive"))
    )
    (net (code "60") (name "Net-(*-VDDA)") (class "Default")
      (node (ref "*") (pin "20") (pinfunction "VREF+_20") (pintype "passive"))
      (node (ref "*") (pin "21") (pinfunction "VDDA_21") (pintype "passive"))
      (node (ref "C10") (pin "1") (pinfunction "1_1") (pintype "passive"))
      (node (ref "C9") (pin "1") (pinfunction "1_1") (pintype "passive"))
      (node (ref "L1") (pin "2") (pinfunction "2_2") (pintype "passive"))
    )
    (net (code "61") (name "Net-(RGB1-B)") (class "Default")
      (node (ref "R1") (pin "1") (pinfunction "1_1") (pintype "passive"))
      (node (ref "RGB1") (pin "3") (pinfunction "B_3") (pintype "passive"))
    )
    (net (code "62") (name "Net-(RGB1-G)") (class "Default")
      (node (ref "R7") (pin "2") (pinfunction "2_2") (pintype "passive"))
      (node (ref "RGB1") (pin "2") (pinfunction "G_2") (pintype "passive"))
    )
    (net (code "63") (name "Net-(RGB1-R)") (class "Default")
      (node (ref "R5") (pin "2") (pinfunction "2_2") (pintype "passive"))
      (node (ref "RGB1") (pin "1") (pinfunction "R_1") (pintype "passive"))
    )
    (net (code "64") (name "Net-(U1-BYP)") (class "Default")
      (node (ref "C19") (pin "2") (pinfunction "2_2") (pintype "passive"))
      (node (ref "U1") (pin "4") (pinfunction "BYP_4") (pintype "passive"))
    )
    (net (code "65") (name "VIN") (class "Default")
      (node (ref "*") (pin "68") (pinfunction "PA9_68") (pintype "passive"))
      (node (ref "C15") (pin "1") (pinfunction "1_1") (pintype "passive"))
      (node (ref "R8") (pin "1") (pinfunction "1_1") (pintype "passive"))
      (node (ref "RGB1") (pin "4") (pinfunction "VCC_4") (pintype "passive"))
      (node (ref "U1") (pin "1") (pinfunction "IN_1") (pintype "passive"))
      (node (ref "U1") (pin "3") (pinfunction "EN_3") (pintype "passive"))
      (node (ref "U2") (pin "1") (pinfunction "IN_1") (pintype "passive"))
      (node (ref "U2") (pin "3") (pinfunction "EN_3") (pintype "passive"))
    )
    (net (code "66") (name "unconnected-(*-PA0_WAKE_UP-Pad22)") (class "Default")
      (node (ref "*") (pin "22") (pinfunction "PA0_WAKE_UP_22") (pintype "passive+no_connect"))
    )
    (net (code "67") (name "unconnected-(*-PA1-Pad23)") (class "Default")
      (node (ref "*") (pin "23") (pinfunction "PA1_23") (pintype "passive+no_connect"))
    )
    (net (code "68") (name "unconnected-(*-PA2-Pad24)") (class "Default")
      (node (ref "*") (pin "24") (pinfunction "PA2_24") (pintype "passive+no_connect"))
    )
    (net (code "69") (name "unconnected-(*-PA3-Pad25)") (class "Default")
      (node (ref "*") (pin "25") (pinfunction "PA3_25") (pintype "passive+no_connect"))
    )
    (net (code "70") (name "unconnected-(*-PA7-Pad31)") (class "Default")
      (node (ref "*") (pin "31") (pinfunction "PA7_31") (pintype "passive+no_connect"))
    )
    (net (code "71") (name "unconnected-(*-PB0-Pad34)") (class "Default")
      (node (ref "*") (pin "34") (pinfunction "PB0_34") (pintype "passive+no_connect"))
    )
    (net (code "72") (name "unconnected-(*-PB1-Pad35)") (class "Default")
      (node (ref "*") (pin "35") (pinfunction "PB1_35") (pintype "passive+no_connect"))
    )
    (net (code "73") (name "unconnected-(*-PB13-Pad43)") (class "Default")
      (node (ref "*") (pin "43") (pinfunction "PB13_43") (pintype "passive+no_connect"))
    )
    (net (code "74") (name "unconnected-(*-PB14-Pad44)") (class "Default")
      (node (ref "*") (pin "44") (pinfunction "PB14_44") (pintype "passive+no_connect"))
    )
    (net (code "75") (name "unconnected-(*-PC3-Pad18)") (class "Default")
      (node (ref "*") (pin "18") (pinfunction "PC3_18") (pintype "passive+no_connect"))
    )
    (net (code "76") (name "unconnected-(*-PC4-Pad32)") (class "Default")
      (node (ref "*") (pin "32") (pinfunction "PC4_32") (pintype "passive+no_connect"))
    )
    (net (code "77") (name "unconnected-(*-PC5-Pad33)") (class "Default")
      (node (ref "*") (pin "33") (pinfunction "PC5_33") (pintype "passive+no_connect"))
    )
    (net (code "78") (name "unconnected-(*-PC13-ANTI_TAMP-Pad7)") (class "Default")
      (node (ref "*") (pin "7") (pinfunction "PC13-ANTI_TAMP_7") (pintype "passive+no_connect"))
    )
    (net (code "79") (name "unconnected-(*-PC14-OSC32_IN-Pad8)") (class "Default")
      (node (ref "*") (pin "8") (pinfunction "PC14-OSC32_IN_8") (pintype "passive+no_connect"))
    )
    (net (code "80") (name "unconnected-(*-PC15-OSC32_OUT-Pad9)") (class "Default")
      (node (ref "*") (pin "9") (pinfunction "PC15-OSC32_OUT_9") (pintype "passive+no_connect"))
    )
    (net (code "81") (name "unconnected-(*-PD1-Pad82)") (class "Default")
      (node (ref "*") (pin "82") (pinfunction "PD1_82") (pintype "passive"))
    )
    (net (code "82") (name "unconnected-(*-PD3-Pad84)") (class "Default")
      (node (ref "*") (pin "84") (pinfunction "PD3_84") (pintype "passive"))
    )
    (net (code "83") (name "unconnected-(*-PD4-Pad85)") (class "Default")
      (node (ref "*") (pin "85") (pinfunction "PD4_85") (pintype "passive"))
    )
    (net (code "84") (name "unconnected-(*-PD5-Pad86)") (class "Default")
      (node (ref "*") (pin "86") (pinfunction "PD5_86") (pintype "passive"))
    )
    (net (code "85") (name "unconnected-(*-PD6-Pad87)") (class "Default")
      (node (ref "*") (pin "87") (pinfunction "PD6_87") (pintype "passive"))
    )
    (net (code "86") (name "unconnected-(*-PD8-Pad55)") (class "Default")
      (node (ref "*") (pin "55") (pinfunction "PD8_55") (pintype "passive"))
    )
    (net (code "87") (name "unconnected-(*-PD9-Pad56)") (class "Default")
      (node (ref "*") (pin "56") (pinfunction "PD9_56") (pintype "passive"))
    )
    (net (code "88") (name "unconnected-(*-PD10-Pad57)") (class "Default")
      (node (ref "*") (pin "57") (pinfunction "PD10_57") (pintype "passive+no_connect"))
    )
    (net (code "89") (name "unconnected-(*-PD11-Pad58)") (class "Default")
      (node (ref "*") (pin "58") (pinfunction "PD11_58") (pintype "passive+no_connect"))
    )
    (net (code "90") (name "unconnected-(*-PD15-Pad62)") (class "Default")
      (node (ref "*") (pin "62") (pinfunction "PD15_62") (pintype "passive+no_connect"))
    )
    (net (code "91") (name "unconnected-(*-PE2-Pad1)") (class "Default")
      (node (ref "*") (pin "1") (pinfunction "PE2_1") (pintype "passive"))
    )
    (net (code "92") (name "unconnected-(*-PE3-Pad2)") (class "Default")
      (node (ref "*") (pin "2") (pinfunction "PE3_2") (pintype "passive+no_connect"))
    )
    (net (code "93") (name "unconnected-(*-PE7-Pad37)") (class "Default")
      (node (ref "*") (pin "37") (pinfunction "PE7_37") (pintype "passive+no_connect"))
    )
    (net (code "94") (name "unconnected-(*-PE8-Pad38)") (class "Default")
      (node (ref "*") (pin "38") (pinfunction "PE8_38") (pintype "passive+no_connect"))
    )
    (net (code "95") (name "unconnected-(*-PE9-Pad39)") (class "Default")
      (node (ref "*") (pin "39") (pinfunction "PE9_39") (pintype "passive+no_connect"))
    )
    (net (code "96") (name "unconnected-(*-PE10-Pad40)") (class "Default")
      (node (ref "*") (pin "40") (pinfunction "PE10_40") (pintype "passive+no_connect"))
    )
    (net (code "97") (name "unconnected-(*-PE11-Pad41)") (class "Default")
      (node (ref "*") (pin "41") (pinfunction "PE11_41") (pintype "passive+no_connect"))
    )
    (net (code "98") (name "unconnected-(*-PE12-Pad42)") (class "Default")
      (node (ref "*") (pin "42") (pinfunction "PE12_42") (pintype "passive+no_connect"))
    )
    (net (code "99") (name "unconnected-(*-PE15-Pad45)") (class "Default")
      (node (ref "*") (pin "45") (pinfunction "PE15_45") (pintype "passive+no_connect"))
    )
    (net (code "100") (name "unconnected-(FPC_7725-Pad1)") (class "Default")
      (node (ref "FPC_7725") (pin "1") (pinfunction "1_1") (pintype "passive+no_connect"))
    )
    (net (code "101") (name "unconnected-(FPC_7725-Pad24)") (class "Default")
      (node (ref "FPC_7725") (pin "24") (pinfunction "24_24") (pintype "passive+no_connect"))
    )
    (net (code "102") (name "unconnected-(FPC_MT9-Pad10)") (class "Default")
      (node (ref "FPC_MT9") (pin "10") (pinfunction "10_10") (pintype "passive+no_connect"))
    )
    (net (code "103") (name "unconnected-(J3-CC1-PadA5)") (class "Default")
      (node (ref "J3") (pin "A5") (pinfunction "CC1_A5") (pintype "passive"))
    )
    (net (code "104") (name "unconnected-(J3-CC2-PadB5)") (class "Default")
      (node (ref "J3") (pin "B5") (pinfunction "CC2_B5") (pintype "passive"))
    )
    (net (code "105") (name "unconnected-(J3-SBU1-PadA8)") (class "Default")
      (node (ref "J3") (pin "A8") (pinfunction "SBU1_A8") (pintype "passive"))
    )
    (net (code "106") (name "unconnected-(J3-SBU2-PadB8)") (class "Default")
      (node (ref "J3") (pin "B8") (pinfunction "SBU2_B8") (pintype "passive"))
    )
    (net (code "107") (name "unconnected-(J3-pad-Pad0)") (class "Default")
      (node (ref "J3") (pin "0") (pinfunction "pad_0") (pintype "passive+no_connect"))
    )
    (net (code "108") (name "unconnected-(J3-pad-Pad0)_1") (class "Default")
      (node (ref "J3") (pin "0") (pinfunction "pad_0") (pintype "passive+no_connect"))
    )
    (net (code "109") (name "unconnected-(J3-pad-Pad0)_2") (class "Default")
      (node (ref "J3") (pin "0") (pinfunction "pad_0") (pintype "passive+no_connect"))
    )
    (net (code "110") (name "unconnected-(J3-pad-Pad0)_3") (class "Default")
      (node (ref "J3") (pin "0") (pinfunction "pad_0") (pintype "passive+no_connect"))
    )
    (net (code "111") (name "unconnected-(U2-BYP-Pad4)") (class "Default")
      (node (ref "U2") (pin "4") (pinfunction "BYP_4") (pintype "passive"))
    )
  )
)
